# SENtral_M_M.net
KiCad netlist of a schematic drawn in Altium Designer
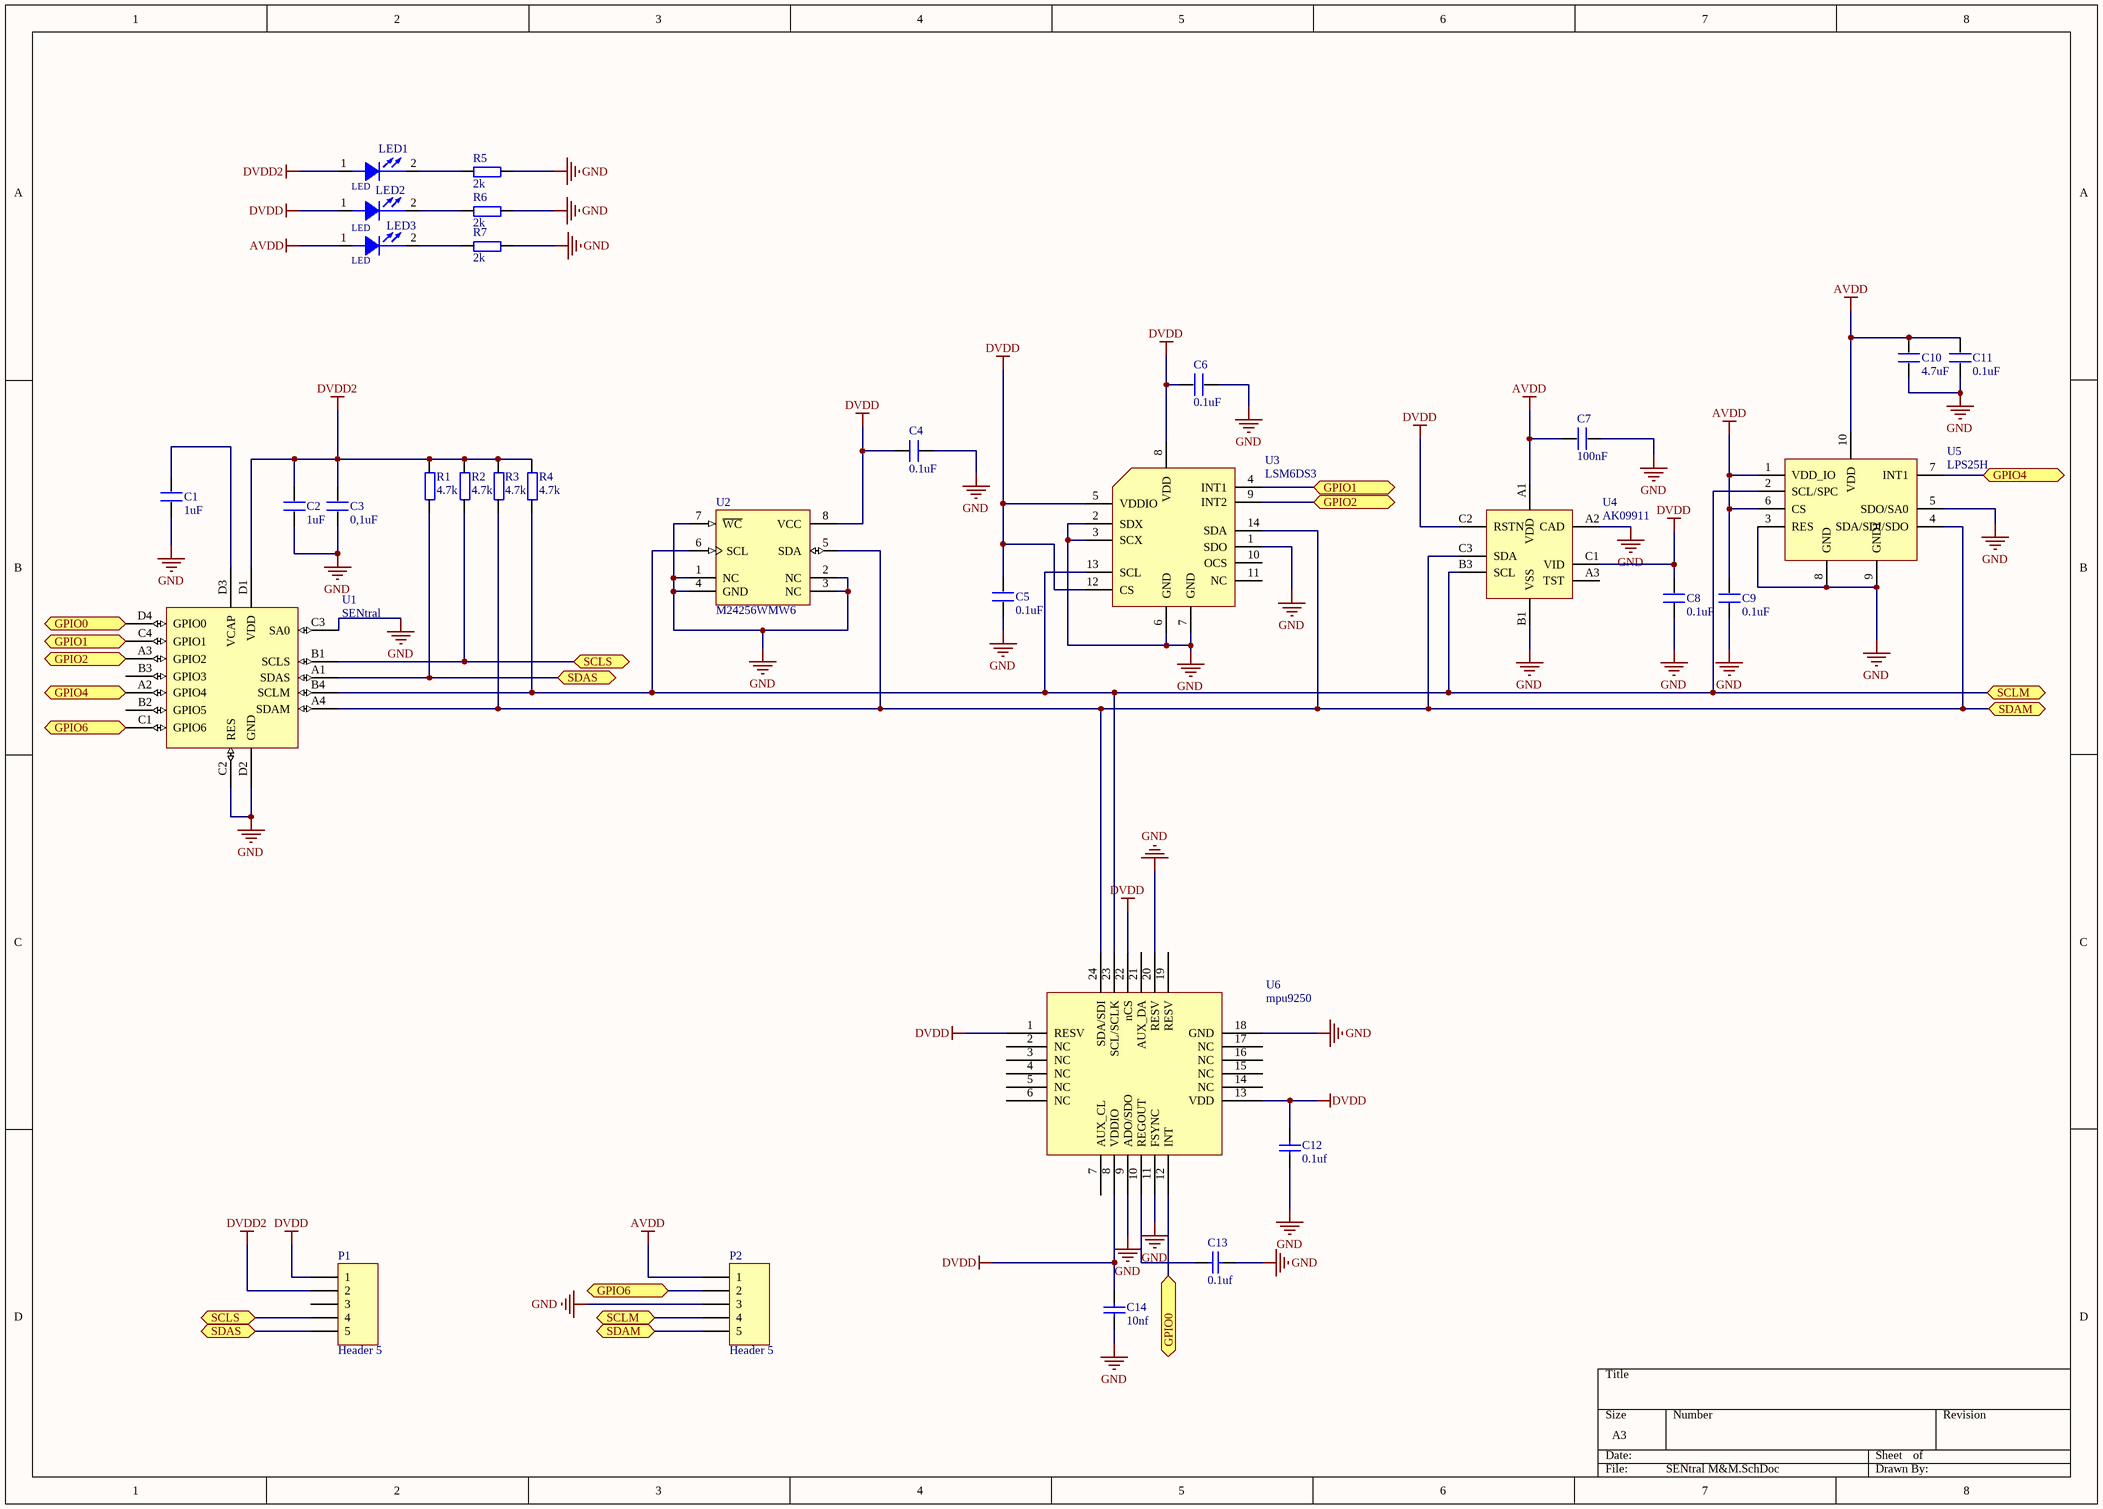
[diagram p0: SENtral M&M.SchDoc]

(export (version "E")
  (design (tool "Eeschema 10.0.6"))
  (components
    (comp (ref "C1") (value "1uF") (footprint "0603") (libsource (lib "three to one") (part "C")))
    (comp (ref "C2") (value "1uF") (footprint "0603") (libsource (lib "three to one") (part "C")))
    (comp (ref "C3") (value "0,1uF") (footprint "0603") (libsource (lib "three to one") (part "C")))
    (comp (ref "C4") (value "0.1uF") (footprint "0603") (libsource (lib "three to one") (part "C")))
    (comp (ref "C5") (value "0.1uF") (footprint "0603") (libsource (lib "three to one") (part "C")))
    (comp (ref "C6") (value "0.1uF") (footprint "0603") (libsource (lib "three to one") (part "C")))
    (comp (ref "C7") (value "100nF") (footprint "0603") (libsource (lib "three to one") (part "C")))
    (comp (ref "C8") (value "0.1uF") (footprint "0603") (libsource (lib "three to one") (part "C")))
    (comp (ref "C9") (value "0.1uF") (footprint "0603") (libsource (lib "three to one") (part "C")))
    (comp (ref "C10") (value "4.7uF") (footprint "0603") (libsource (lib "three to one") (part "C")))
    (comp (ref "C11") (value "0.1uF") (footprint "0603") (libsource (lib "three to one") (part "C")))
    (comp (ref "C12")
      (value "0.1uf")
      (footprint "CAPC1608L")
      (description "Capacitor")
      (fields (field (name "Comment") "Cap") (field (name "PUBLISHER") "Altium Limited"))
      (libsource (lib "ADNS+MPU") (part "Cap_2"))
    )
    (comp (ref "C13")
      (value "0.1uf")
      (footprint "CAPC1608L")
      (description "Capacitor")
      (fields (field (name "Comment") "Cap") (field (name "PUBLISHER") "Altium Limited"))
      (libsource (lib "ADNS+MPU") (part "Cap"))
    )
    (comp (ref "C14")
      (value "10nf")
      (footprint "CAPC1608L")
      (description "Capacitor")
      (fields (field (name "Comment") "Cap") (field (name "PUBLISHER") "Altium Limited"))
      (libsource (lib "ADNS+MPU") (part "Cap_1"))
    )
    (comp (ref "LED1") (value "LED") (footprint "SMDLED-0603") (libsource (lib "three to one") (part "LED")))
    (comp (ref "LED2") (value "LED") (footprint "SMDLED-0603") (libsource (lib "three to one") (part "LED")))
    (comp (ref "LED3") (value "LED") (footprint "SMDLED-0603") (libsource (lib "three to one") (part "LED")))
    (comp (ref "P1")
      (value "Header 5")
      (footprint "HDR1X5")
      (description "Header, 5-Pin")
      (fields (field (name "PUBLISHER") "Altium Limited"))
      (libsource (lib "Miscellaneous Connectors") (part "Header 5"))
    )
    (comp (ref "P2")
      (value "Header 5")
      (footprint "HDR1X5")
      (description "Header, 5-Pin")
      (fields (field (name "PUBLISHER") "Altium Limited"))
      (libsource (lib "Miscellaneous Connectors") (part "Header 5"))
    )
    (comp (ref "R1")
      (value "4.7k")
      (footprint "0603P")
      (description "贴片电阻")
      (libsource (lib "three to one") (part "R"))
    )
    (comp (ref "R2")
      (value "4.7k")
      (footprint "0603P")
      (description "贴片电阻")
      (libsource (lib "three to one") (part "R"))
    )
    (comp (ref "R3")
      (value "4.7k")
      (footprint "0603P")
      (description "贴片电阻")
      (libsource (lib "three to one") (part "R"))
    )
    (comp (ref "R4")
      (value "4.7k")
      (footprint "0603P")
      (description "贴片电阻")
      (libsource (lib "three to one") (part "R"))
    )
    (comp (ref "R5")
      (value "2k")
      (footprint "0603P")
      (description "贴片电阻")
      (libsource (lib "three to one") (part "R"))
    )
    (comp (ref "R6")
      (value "2k")
      (footprint "0603P")
      (description "贴片电阻")
      (libsource (lib "three to one") (part "R"))
    )
    (comp (ref "R7")
      (value "2k")
      (footprint "0603P")
      (description "贴片电阻")
      (libsource (lib "three to one") (part "R"))
    )
    (comp (ref "U1")
      (value "SENtral")
      (footprint "BGA16C40P4X4_160X160X51")
      (description "PNI SENtral")
      (libsource (lib "CJ_Component") (part "SENtral"))
    )
    (comp (ref "U2")
      (value "M24256WMW6")
      (footprint "SO8W_N")
      (description "256 Kbit Serial I睠 Bus EEPROM without Chip Enable Lines")
      (fields (field (name "PUBLISHER") "Altium Limited"))
      (libsource (lib "ST Memory EEPROM Serial") (part "M24256WMW6"))
    )
    (comp (ref "U3")
      (value "LSM6DS3")
      (footprint "LGA-14L")
      (libsource (lib "CJ_Component") (part "LSM6DS3"))
    )
    (comp (ref "U4") (value "AK09911") (footprint "UFBGA8") (libsource (lib "CJ_Component") (part "AK09911")))
    (comp (ref "U5") (value "LPS25H") (footprint "HLGA-10L") (libsource (lib "CJ_Component") (part "LPS25H")))
    (comp (ref "U6") (value "mpu9250") (footprint "mpu9250") (libsource (lib "ADNS+MPU") (part "mpu9250")))
  )
  (nets
    (net (code "1") (name "/GPIO0") (class "Default")
      (node (ref "U1") (pin "D4") (pinfunction "GPIO0_D4") (pintype "bidirectional"))
      (node (ref "U6") (pin "12") (pinfunction "INT_12") (pintype "passive"))
    )
    (net (code "2") (name "/GPIO1") (class "Default")
      (node (ref "U1") (pin "C4") (pinfunction "GPIO1_C4") (pintype "bidirectional"))
      (node (ref "U3") (pin "4") (pinfunction "INT1_4") (pintype "passive"))
    )
    (net (code "3") (name "/GPIO2") (class "Default")
      (node (ref "U1") (pin "A3") (pinfunction "GPIO2_A3") (pintype "bidirectional"))
      (node (ref "U3") (pin "9") (pinfunction "INT2_9") (pintype "passive"))
    )
    (net (code "4") (name "/GPIO4") (class "Default")
      (node (ref "U1") (pin "A2") (pinfunction "GPIO4_A2") (pintype "bidirectional"))
      (node (ref "U5") (pin "7") (pinfunction "INT1_7") (pintype "passive"))
    )
    (net (code "5") (name "/GPIO6") (class "Default")
      (node (ref "P2") (pin "2") (pinfunction "2_2") (pintype "passive"))
      (node (ref "U1") (pin "C1") (pinfunction "GPIO6_C1") (pintype "bidirectional"))
    )
    (net (code "6") (name "/SCLM") (class "Default")
      (node (ref "P2") (pin "4") (pinfunction "4_4") (pintype "passive"))
      (node (ref "R4") (pin "1") (pintype "passive"))
      (node (ref "U1") (pin "B4") (pinfunction "SCLM_B4") (pintype "bidirectional"))
      (node (ref "U2") (pin "6") (pinfunction "SCL_6") (pintype "input"))
      (node (ref "U3") (pin "13") (pinfunction "SCL_13") (pintype "passive"))
      (node (ref "U4") (pin "B3") (pinfunction "SCL_B3") (pintype "passive"))
      (node (ref "U5") (pin "2") (pinfunction "SCL/SPC_2") (pintype "passive"))
      (node (ref "U6") (pin "23") (pinfunction "SCL/SCLK_23") (pintype "passive"))
    )
    (net (code "7") (name "/SCLS") (class "Default")
      (node (ref "P1") (pin "4") (pinfunction "4_4") (pintype "passive"))
      (node (ref "R2") (pin "1") (pintype "passive"))
      (node (ref "U1") (pin "B1") (pinfunction "SCLS_B1") (pintype "bidirectional"))
    )
    (net (code "8") (name "/SDAM") (class "Default")
      (node (ref "P2") (pin "5") (pinfunction "5_5") (pintype "passive"))
      (node (ref "R3") (pin "1") (pintype "passive"))
      (node (ref "U1") (pin "A4") (pinfunction "SDAM_A4") (pintype "bidirectional"))
      (node (ref "U2") (pin "5") (pinfunction "SDA_5") (pintype "bidirectional"))
      (node (ref "U3") (pin "14") (pinfunction "SDA_14") (pintype "passive"))
      (node (ref "U4") (pin "C3") (pinfunction "SDA_C3") (pintype "passive"))
      (node (ref "U5") (pin "4") (pinfunction "SDA/SDI/SDO_4") (pintype "passive"))
      (node (ref "U6") (pin "24") (pinfunction "SDA/SDI_24") (pintype "passive"))
    )
    (net (code "9") (name "/SDAS") (class "Default")
      (node (ref "P1") (pin "5") (pinfunction "5_5") (pintype "passive"))
      (node (ref "R1") (pin "1") (pintype "passive"))
      (node (ref "U1") (pin "A1") (pinfunction "SDAS_A1") (pintype "bidirectional"))
    )
    (net (code "10") (name "AVDD") (class "Default")
      (node (ref "C10") (pin "1") (pintype "passive"))
      (node (ref "C11") (pin "1") (pintype "passive"))
      (node (ref "C7") (pin "1") (pintype "passive"))
      (node (ref "C9") (pin "1") (pintype "passive"))
      (node (ref "LED3") (pin "1") (pinfunction "ANODE_1") (pintype "passive"))
      (node (ref "P2") (pin "1") (pinfunction "1_1") (pintype "passive"))
      (node (ref "U4") (pin "A1") (pinfunction "VDD_A1") (pintype "passive"))
      (node (ref "U5") (pin "1") (pinfunction "VDD_IO_1") (pintype "passive"))
      (node (ref "U5") (pin "10") (pinfunction "VDD_10") (pintype "passive"))
      (node (ref "U5") (pin "6") (pinfunction "CS_6") (pintype "passive"))
    )
    (net (code "11") (name "DVDD") (class "Default")
      (node (ref "C12") (pin "2") (pinfunction "2_2") (pintype "passive"))
      (node (ref "C14") (pin "2") (pinfunction "2_2") (pintype "passive"))
      (node (ref "C4") (pin "1") (pintype "passive"))
      (node (ref "C5") (pin "1") (pintype "passive"))
      (node (ref "C6") (pin "1") (pintype "passive"))
      (node (ref "C8") (pin "1") (pintype "passive"))
      (node (ref "LED2") (pin "1") (pinfunction "ANODE_1") (pintype "passive"))
      (node (ref "P1") (pin "1") (pinfunction "1_1") (pintype "passive"))
      (node (ref "U2") (pin "8") (pinfunction "VCC_8") (pintype "power_in"))
      (node (ref "U3") (pin "12") (pinfunction "CS_12") (pintype "passive"))
      (node (ref "U3") (pin "5") (pinfunction "VDDIO_5") (pintype "passive"))
      (node (ref "U3") (pin "8") (pinfunction "VDD_8") (pintype "passive"))
      (node (ref "U4") (pin "C1") (pinfunction "VID_C1") (pintype "passive"))
      (node (ref "U4") (pin "C2") (pinfunction "RSTN_C2") (pintype "passive"))
      (node (ref "U6") (pin "1") (pinfunction "RESV_1") (pintype "passive"))
      (node (ref "U6") (pin "13") (pinfunction "VDD_13") (pintype "passive"))
      (node (ref "U6") (pin "22") (pinfunction "nCS_22") (pintype "passive"))
      (node (ref "U6") (pin "8") (pinfunction "VDDIO_8") (pintype "passive"))
    )
    (net (code "12") (name "DVDD2") (class "Default")
      (node (ref "C2") (pin "1") (pintype "passive"))
      (node (ref "C3") (pin "1") (pintype "passive"))
      (node (ref "LED1") (pin "1") (pinfunction "ANODE_1") (pintype "passive"))
      (node (ref "P1") (pin "2") (pinfunction "2_2") (pintype "passive"))
      (node (ref "R1") (pin "2") (pintype "passive"))
      (node (ref "R2") (pin "2") (pintype "passive"))
      (node (ref "R3") (pin "2") (pintype "passive"))
      (node (ref "R4") (pin "2") (pintype "passive"))
      (node (ref "U1") (pin "D1") (pinfunction "VDD_D1") (pintype "power_in"))
    )
    (net (code "13") (name "GND") (class "Default")
      (node (ref "C1") (pin "2") (pintype "passive"))
      (node (ref "C10") (pin "2") (pintype "passive"))
      (node (ref "C11") (pin "2") (pintype "passive"))
      (node (ref "C12") (pin "1") (pinfunction "1_1") (pintype "passive"))
      (node (ref "C13") (pin "2") (pinfunction "2_2") (pintype "passive"))
      (node (ref "C14") (pin "1") (pinfunction "1_1") (pintype "passive"))
      (node (ref "C2") (pin "2") (pintype "passive"))
      (node (ref "C3") (pin "2") (pintype "passive"))
      (node (ref "C4") (pin "2") (pintype "passive"))
      (node (ref "C5") (pin "2") (pintype "passive"))
      (node (ref "C6") (pin "2") (pintype "passive"))
      (node (ref "C7") (pin "2") (pintype "passive"))
      (node (ref "C8") (pin "2") (pintype "passive"))
      (node (ref "C9") (pin "2") (pintype "passive"))
      (node (ref "P2") (pin "3") (pinfunction "3_3") (pintype "passive"))
      (node (ref "R5") (pin "2") (pintype "passive"))
      (node (ref "R6") (pin "2") (pintype "passive"))
      (node (ref "R7") (pin "2") (pintype "passive"))
      (node (ref "U1") (pin "C2") (pinfunction "RES_C2") (pintype "bidirectional"))
      (node (ref "U1") (pin "C3") (pinfunction "SA0_C3") (pintype "bidirectional"))
      (node (ref "U1") (pin "D2") (pinfunction "GND_D2") (pintype "power_in"))
      (node (ref "U2") (pin "1") (pinfunction "NC_1") (pintype "passive"))
      (node (ref "U2") (pin "2") (pinfunction "NC_2") (pintype "passive"))
      (node (ref "U2") (pin "3") (pinfunction "NC_3") (pintype "passive"))
      (node (ref "U2") (pin "4") (pinfunction "GND_4") (pintype "power_in"))
      (node (ref "U2") (pin "7") (pinfunction "~{WC}_7") (pintype "input"))
      (node (ref "U3") (pin "1") (pinfunction "SDO_1") (pintype "passive"))
      (node (ref "U3") (pin "2") (pinfunction "SDX_2") (pintype "passive"))
      (node (ref "U3") (pin "3") (pinfunction "SCX_3") (pintype "passive"))
      (node (ref "U3") (pin "6") (pinfunction "GND_6") (pintype "passive"))
      (node (ref "U3") (pin "7") (pinfunction "GND_7") (pintype "passive"))
      (node (ref "U4") (pin "A2") (pinfunction "CAD_A2") (pintype "passive"))
      (node (ref "U4") (pin "B1") (pinfunction "VSS_B1") (pintype "passive"))
      (node (ref "U5") (pin "3") (pinfunction "RES_3") (pintype "passive"))
      (node (ref "U5") (pin "5") (pinfunction "SDO/SA0_5") (pintype "passive"))
      (node (ref "U5") (pin "8") (pinfunction "GND_8") (pintype "passive"))
      (node (ref "U5") (pin "9") (pinfunction "GND1_9") (pintype "passive"))
      (node (ref "U6") (pin "11") (pinfunction "FSYNC_11") (pintype "passive"))
      (node (ref "U6") (pin "18") (pinfunction "GND_18") (pintype "passive"))
      (node (ref "U6") (pin "20") (pinfunction "RESV_20") (pintype "passive"))
      (node (ref "U6") (pin "9") (pinfunction "ADO/SDO_9") (pintype "passive"))
    )
    (net (code "14") (name "Net-(LED1-CATHODE)") (class "Default")
      (node (ref "LED1") (pin "2") (pinfunction "CATHODE_2") (pintype "passive"))
      (node (ref "R5") (pin "1") (pintype "passive"))
    )
    (net (code "15") (name "Net-(LED2-CATHODE)") (class "Default")
      (node (ref "LED2") (pin "2") (pinfunction "CATHODE_2") (pintype "passive"))
      (node (ref "R6") (pin "1") (pintype "passive"))
    )
    (net (code "16") (name "Net-(LED3-CATHODE)") (class "Default")
      (node (ref "LED3") (pin "2") (pinfunction "CATHODE_2") (pintype "passive"))
      (node (ref "R7") (pin "1") (pintype "passive"))
    )
    (net (code "17") (name "Net-(U1-VCAP)") (class "Default")
      (node (ref "C1") (pin "1") (pintype "passive"))
      (node (ref "U1") (pin "D3") (pinfunction "VCAP_D3") (pintype "passive"))
    )
    (net (code "18") (name "Net-(U6-REGOUT)") (class "Default")
      (node (ref "C13") (pin "1") (pinfunction "1_1") (pintype "passive"))
      (node (ref "U6") (pin "10") (pinfunction "REGOUT_10") (pintype "passive"))
    )
    (net (code "19") (name "unconnected-(P1-Pad3)") (class "Default")
      (node (ref "P1") (pin "3") (pinfunction "3_3") (pintype "passive"))
    )
    (net (code "20") (name "unconnected-(U1-GPIO3-PadB3)") (class "Default")
      (node (ref "U1") (pin "B3") (pinfunction "GPIO3_B3") (pintype "bidirectional"))
    )
    (net (code "21") (name "unconnected-(U1-GPIO5-PadB2)") (class "Default")
      (node (ref "U1") (pin "B2") (pinfunction "GPIO5_B2") (pintype "bidirectional"))
    )
    (net (code "22") (name "unconnected-(U3-NC-Pad11)") (class "Default")
      (node (ref "U3") (pin "11") (pinfunction "NC_11") (pintype "passive"))
    )
    (net (code "23") (name "unconnected-(U3-OCS-Pad10)") (class "Default")
      (node (ref "U3") (pin "10") (pinfunction "OCS_10") (pintype "passive"))
    )
    (net (code "24") (name "unconnected-(U4-TST-PadA3)") (class "Default")
      (node (ref "U4") (pin "A3") (pinfunction "TST_A3") (pintype "passive"))
    )
    (net (code "25") (name "unconnected-(U6-AUX_CL-Pad7)") (class "Default")
      (node (ref "U6") (pin "7") (pinfunction "AUX_CL_7") (pintype "passive"))
    )
    (net (code "26") (name "unconnected-(U6-AUX_DA-Pad21)") (class "Default")
      (node (ref "U6") (pin "21") (pinfunction "AUX_DA_21") (pintype "passive"))
    )
    (net (code "27") (name "unconnected-(U6-NC-Pad2)") (class "Default")
      (node (ref "U6") (pin "2") (pinfunction "NC_2") (pintype "passive"))
    )
    (net (code "28") (name "unconnected-(U6-NC-Pad3)") (class "Default")
      (node (ref "U6") (pin "3") (pinfunction "NC_3") (pintype "passive"))
    )
    (net (code "29") (name "unconnected-(U6-NC-Pad4)") (class "Default")
      (node (ref "U6") (pin "4") (pinfunction "NC_4") (pintype "passive"))
    )
    (net (code "30") (name "unconnected-(U6-NC-Pad5)") (class "Default")
      (node (ref "U6") (pin "5") (pinfunction "NC_5") (pintype "passive"))
    )
    (net (code "31") (name "unconnected-(U6-NC-Pad6)") (class "Default")
      (node (ref "U6") (pin "6") (pinfunction "NC_6") (pintype "passive"))
    )
    (net (code "32") (name "unconnected-(U6-NC-Pad14)") (class "Default")
      (node (ref "U6") (pin "14") (pinfunction "NC_14") (pintype "passive"))
    )
    (net (code "33") (name "unconnected-(U6-NC-Pad15)") (class "Default")
      (node (ref "U6") (pin "15") (pinfunction "NC_15") (pintype "passive"))
    )
    (net (code "34") (name "unconnected-(U6-NC-Pad16)") (class "Default")
      (node (ref "U6") (pin "16") (pinfunction "NC_16") (pintype "passive"))
    )
    (net (code "35") (name "unconnected-(U6-NC-Pad17)") (class "Default")
      (node (ref "U6") (pin "17") (pinfunction "NC_17") (pintype "passive"))
    )
    (net (code "36") (name "unconnected-(U6-RESV-Pad19)") (class "Default")
      (node (ref "U6") (pin "19") (pinfunction "RESV_19") (pintype "passive"))
    )
  )
)
